# design.net
KiCad netlist of a schematic drawn in Altium Designer
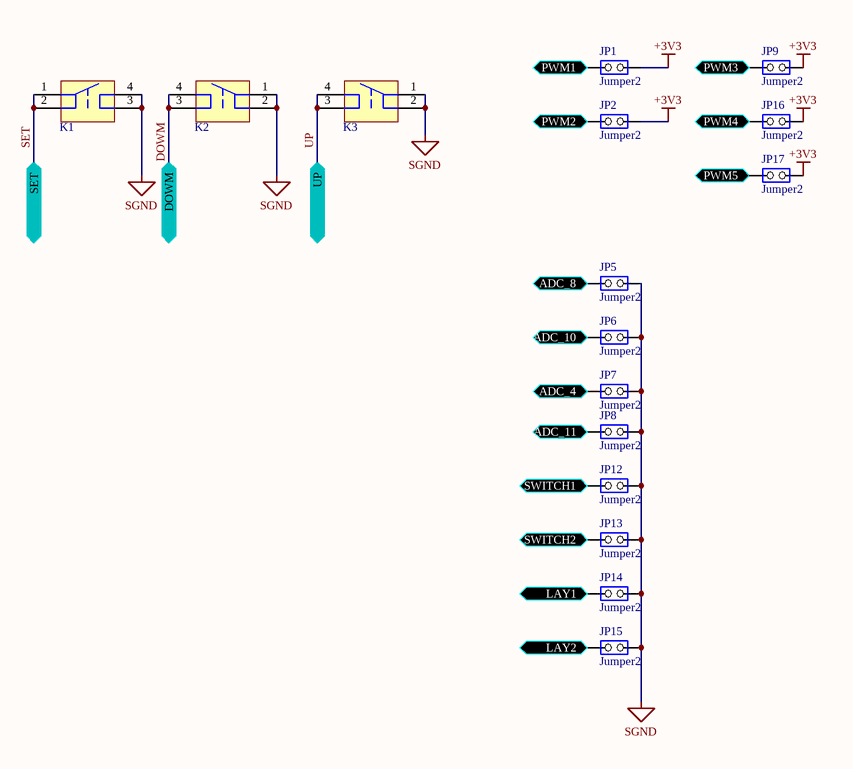
[diagram p0: 用户输入.SchDoc]

(export (version "E")
  (design (tool "Eeschema 10.0.6"))
  (components
    (comp (ref "JP1")
      (value "Jumper2")
      (footprint "CON2-P2.54")
      (libsource (lib "Miscellaneous Connectors") (part "Jumper2"))
    )
    (comp (ref "JP2")
      (value "Jumper2")
      (footprint "CON2-P2.54")
      (libsource (lib "Miscellaneous Connectors") (part "Jumper2"))
    )
    (comp (ref "JP5")
      (value "Jumper2")
      (footprint "CON2-P2.54")
      (libsource (lib "Miscellaneous Connectors") (part "Jumper2"))
    )
    (comp (ref "JP6")
      (value "Jumper2")
      (footprint "CON2-P2.54")
      (libsource (lib "Miscellaneous Connectors") (part "Jumper2"))
    )
    (comp (ref "JP7")
      (value "Jumper2")
      (footprint "CON2-P2.54")
      (libsource (lib "Miscellaneous Connectors") (part "Jumper2"))
    )
    (comp (ref "JP8")
      (value "Jumper2")
      (footprint "CON2-P2.54")
      (libsource (lib "Miscellaneous Connectors") (part "Jumper2"))
    )
    (comp (ref "JP9")
      (value "Jumper2")
      (footprint "CON2-P2.54")
      (libsource (lib "Miscellaneous Connectors") (part "Jumper2"))
    )
    (comp (ref "JP12")
      (value "Jumper2")
      (footprint "CON2-P2.54")
      (libsource (lib "Miscellaneous Connectors") (part "Jumper2"))
    )
    (comp (ref "JP13")
      (value "Jumper2")
      (footprint "CON2-P2.54")
      (libsource (lib "Miscellaneous Connectors") (part "Jumper2"))
    )
    (comp (ref "JP14")
      (value "Jumper2")
      (footprint "CON2-P2.54")
      (libsource (lib "Miscellaneous Connectors") (part "Jumper2"))
    )
    (comp (ref "JP15")
      (value "Jumper2")
      (footprint "CON2-P2.54")
      (libsource (lib "Miscellaneous Connectors") (part "Jumper2"))
    )
    (comp (ref "JP16")
      (value "Jumper2")
      (footprint "CON2-P2.54")
      (libsource (lib "Miscellaneous Connectors") (part "Jumper2"))
    )
    (comp (ref "JP17")
      (value "Jumper2")
      (footprint "CON2-P2.54")
      (libsource (lib "Miscellaneous Connectors") (part "Jumper2"))
    )
    (comp (ref "K1")
      (value "12*12")
      (footprint "按键6*6贴片")
      (description "按键")
      (libsource (lib "Miscellaneous Devices") (part "Button"))
    )
    (comp (ref "K2")
      (value "12*12")
      (footprint "按键6*6贴片")
      (description "按键")
      (libsource (lib "") (part "Button_1"))
    )
    (comp (ref "K3")
      (value "12*12")
      (footprint "按键6*6贴片")
      (description "按键")
      (libsource (lib "") (part "Button_1"))
    )
  )
  (nets
    (net (code "1") (name "+3V3") (class "Default")
      (node (ref "JP1") (pin "2") (pinfunction "NO_2") (pintype "passive"))
      (node (ref "JP16") (pin "2") (pinfunction "NO_2") (pintype "passive"))
      (node (ref "JP17") (pin "2") (pinfunction "NO_2") (pintype "passive"))
      (node (ref "JP2") (pin "2") (pinfunction "NO_2") (pintype "passive"))
      (node (ref "JP9") (pin "2") (pinfunction "NO_2") (pintype "passive"))
    )
    (net (code "2") (name "/ADC_4") (class "Default")
      (node (ref "JP7") (pin "1") (pinfunction "COMMON_1") (pintype "passive"))
    )
    (net (code "3") (name "/ADC_8") (class "Default")
      (node (ref "JP5") (pin "1") (pinfunction "COMMON_1") (pintype "passive"))
    )
    (net (code "4") (name "/ADC_10") (class "Default")
      (node (ref "JP6") (pin "1") (pinfunction "COMMON_1") (pintype "passive"))
    )
    (net (code "5") (name "/ADC_11") (class "Default")
      (node (ref "JP8") (pin "1") (pinfunction "COMMON_1") (pintype "passive"))
    )
    (net (code "6") (name "/DOWM") (class "Default")
      (node (ref "K2") (pin "3") (pinfunction "3_3") (pintype "passive"))
      (node (ref "K2") (pin "4") (pinfunction "4_4") (pintype "passive"))
    )
    (net (code "7") (name "/LAY1") (class "Default")
      (node (ref "JP14") (pin "1") (pinfunction "COMMON_1") (pintype "passive"))
    )
    (net (code "8") (name "/LAY2") (class "Default")
      (node (ref "JP15") (pin "1") (pinfunction "COMMON_1") (pintype "passive"))
    )
    (net (code "9") (name "/PWM1") (class "Default")
      (node (ref "JP1") (pin "1") (pinfunction "COMMON_1") (pintype "passive"))
    )
    (net (code "10") (name "/PWM2") (class "Default")
      (node (ref "JP2") (pin "1") (pinfunction "COMMON_1") (pintype "passive"))
    )
    (net (code "11") (name "/PWM3") (class "Default")
      (node (ref "JP9") (pin "1") (pinfunction "COMMON_1") (pintype "passive"))
    )
    (net (code "12") (name "/PWM4") (class "Default")
      (node (ref "JP16") (pin "1") (pinfunction "COMMON_1") (pintype "passive"))
    )
    (net (code "13") (name "/PWM5") (class "Default")
      (node (ref "JP17") (pin "1") (pinfunction "COMMON_1") (pintype "passive"))
    )
    (net (code "14") (name "/SET") (class "Default")
      (node (ref "K1") (pin "1") (pinfunction "1_1") (pintype "passive"))
      (node (ref "K1") (pin "2") (pinfunction "2_2") (pintype "passive"))
    )
    (net (code "15") (name "/SWITCH1") (class "Default")
      (node (ref "JP12") (pin "1") (pinfunction "COMMON_1") (pintype "passive"))
    )
    (net (code "16") (name "/SWITCH2") (class "Default")
      (node (ref "JP13") (pin "1") (pinfunction "COMMON_1") (pintype "passive"))
    )
    (net (code "17") (name "/UP") (class "Default")
      (node (ref "K3") (pin "3") (pinfunction "3_3") (pintype "passive"))
      (node (ref "K3") (pin "4") (pinfunction "4_4") (pintype "passive"))
    )
    (net (code "18") (name "SGND") (class "Default")
      (node (ref "JP12") (pin "2") (pinfunction "NO_2") (pintype "passive"))
      (node (ref "JP13") (pin "2") (pinfunction "NO_2") (pintype "passive"))
      (node (ref "JP14") (pin "2") (pinfunction "NO_2") (pintype "passive"))
      (node (ref "JP15") (pin "2") (pinfunction "NO_2") (pintype "passive"))
      (node (ref "JP5") (pin "2") (pinfunction "NO_2") (pintype "passive"))
      (node (ref "JP6") (pin "2") (pinfunction "NO_2") (pintype "passive"))
      (node (ref "JP7") (pin "2") (pinfunction "NO_2") (pintype "passive"))
      (node (ref "JP8") (pin "2") (pinfunction "NO_2") (pintype "passive"))
      (node (ref "K1") (pin "3") (pinfunction "3_3") (pintype "passive"))
      (node (ref "K1") (pin "4") (pinfunction "4_4") (pintype "passive"))
      (node (ref "K2") (pin "1") (pinfunction "1_1") (pintype "passive"))
      (node (ref "K2") (pin "2") (pinfunction "2_2") (pintype "passive"))
      (node (ref "K3") (pin "1") (pinfunction "1_1") (pintype "passive"))
      (node (ref "K3") (pin "2") (pinfunction "2_2") (pintype "passive"))
    )
  )
)
